# FeatherWing.net
KiCad netlist of a schematic drawn in EAGLE
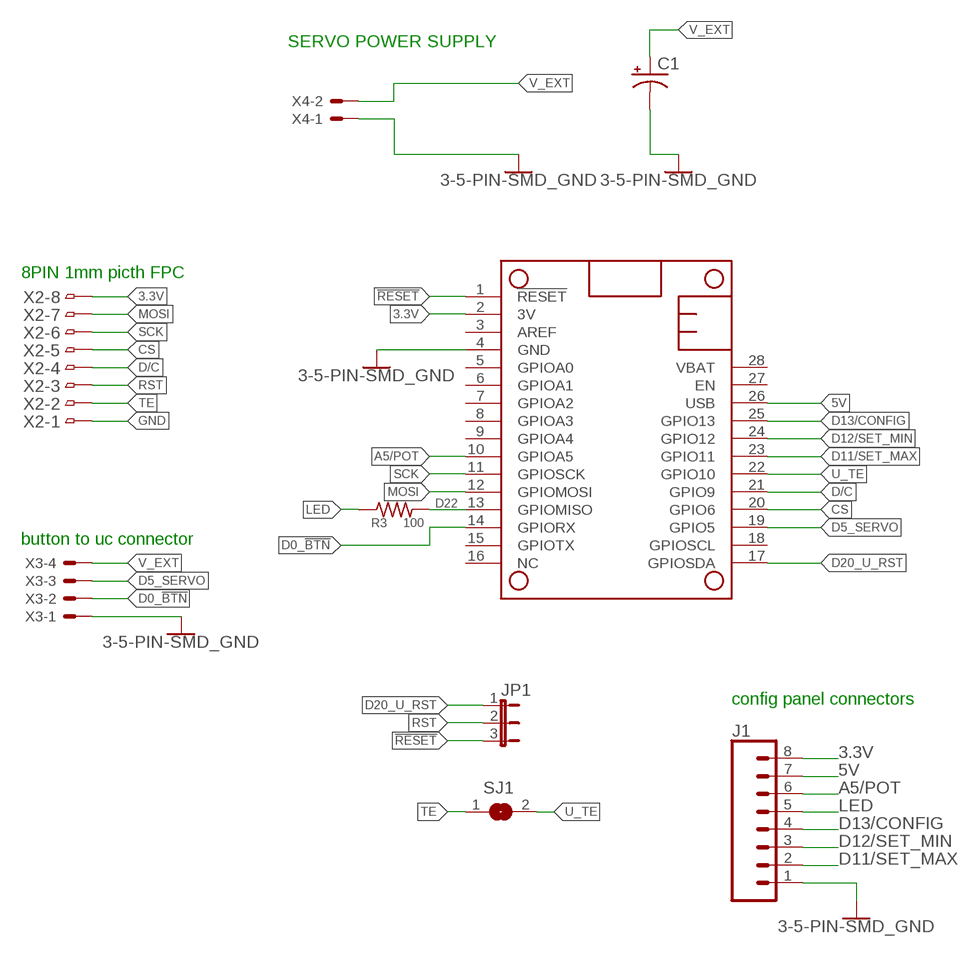
[diagram p0: schematic, sheet 1]

(export (version "E")
  (design (tool "Eeschema 10.0.6"))
  (components
    (comp (ref "C1")
      (value "ADAFRUIT_CNCT_NFP_CPOL-USC/6032-28R")
      (footprint "eagle-import:ADAFRUIT_CNCT_NFP_C_6032-28R")
      (libsource (lib "eagle-import") (part "ADAFRUIT_CNCT_NFP_CPOL-USC/6032-28R"))
    )
    (comp (ref "J1")
      (value "SPARKFUN-CONNECTORS_CONN_08LONGPADS")
      (footprint "eagle-import:SPARKFUN-CONNECTORS_1X08_LONGPADS")
      (libsource (lib "eagle-import") (part "SPARKFUN-CONNECTORS_CONN_08LONGPADS"))
    )
    (comp (ref "JP1")
      (value "LED-BADGE_SCHEMATIC_JUMPER_JP2E")
      (footprint "eagle-import:LED-BADGE_SCHEMATIC_JUMPER_JP2")
      (libsource (lib "eagle-import") (part "LED-BADGE_SCHEMATIC_JUMPER_JP2E"))
    )
    (comp (ref "MS1")
      (value "ADAFRUIT_FEATHERWING")
      (footprint "eagle-import:ADAFRUIT_FEATHERWING")
      (libsource (lib "eagle-import") (part "ADAFRUIT_FEATHERWING"))
    )
    (comp (ref "R3")
      (value "100")
      (footprint "eagle-import:AIRPOCKETCELL_ARDUINO_3V_TTL_INTERFACE_2_PI_ADAFRUIT_M0805")
      (libsource (lib "eagle-import") (part "AIRPOCKETCELL_ARDUINO_3V_TTL_INTERFACE_2_PI_ADAFRUIT_R-US_M0805"))
    )
    (comp (ref "SJ1")
      (value "AIRPOCKETCELL_JUMPER_SJW")
      (footprint "eagle-import:AIRPOCKETCELL_JUMPER_SJW")
      (libsource (lib "eagle-import") (part "AIRPOCKETCELL_JUMPER_SJW"))
    )
    (comp (ref "X2")
      (value "LEDMATRIXFPCCONNECTOR_CON-HIROSE_FH12-08S-1SH")
      (footprint "eagle-import:LEDMATRIXFPCCONNECTOR_CON-HIROSE_FH12-08S-1SH")
      (libsource (lib "eagle-import") (part "LEDMATRIXFPCCONNECTOR_CON-HIROSE_FH12-08S-1SH"))
    )
    (comp (ref "X3")
      (value "REMBRANDT-ELECTRONICS---JST-XH-CONNECTORS-V1-0_JST-XH-04-PIN-LONG-PAD")
      (footprint "eagle-import:REMBRANDT-ELECTRONICS---JST-XH-CONNECTORS-V1-0_JST-XH-04-PACKAGE-LONG-PAD")
      (libsource (lib "eagle-import") (part "REMBRANDT-ELECTRONICS---JST-XH-CONNECTORS-V1-0_JST-XH-04-PIN-LONG-PAD"))
    )
    (comp (ref "X4")
      (value "REMBRANDT-ELECTRONICS---JST-XH-CONNECTORS-V1-0_JST-XH-02-PIN-LONG-PAD")
      (footprint "eagle-import:REMBRANDT-ELECTRONICS---JST-XH-CONNECTORS-V1-0_JST-XH-02-PACKAGE-LONG-PAD")
      (libsource (lib "eagle-import") (part "REMBRANDT-ELECTRONICS---JST-XH-CONNECTORS-V1-0_JST-XH-02-PIN-LONG-PAD"))
    )
  )
  (nets
    (net (code "1") (name "/D0_~{BTN}") (class "Default")
      (node (ref "MS1") (pin "14") (pinfunction "GPIORX_14") (pintype "bidirectional"))
      (node (ref "X3") (pin "2") (pinfunction "S_2") (pintype "passive"))
    )
    (net (code "2") (name "/D22") (class "Default")
      (node (ref "MS1") (pin "13") (pinfunction "GPIOMISO_13") (pintype "bidirectional"))
      (node (ref "R3") (pin "2") (pinfunction "2_2") (pintype "passive"))
    )
    (net (code "3") (name "/VBAT") (class "Default")
      (node (ref "MS1") (pin "28") (pinfunction "VBAT_28") (pintype "power_in"))
    )
    (net (code "4") (name "/~{RESET}") (class "Default")
      (node (ref "JP1") (pin "3") (pinfunction "3_3") (pintype "passive"))
      (node (ref "MS1") (pin "1") (pinfunction "~{RESET}_1") (pintype "input"))
    )
    (net (code "5") (name "3.3V") (class "Default")
      (node (ref "J1") (pin "8") (pinfunction "8_8") (pintype "passive"))
      (node (ref "MS1") (pin "2") (pinfunction "3V_2") (pintype "power_in"))
      (node (ref "X2") (pin "8") (pinfunction "1_8") (pintype "passive"))
    )
    (net (code "6") (name "5V") (class "Default")
      (node (ref "J1") (pin "7") (pinfunction "7_7") (pintype "passive"))
      (node (ref "MS1") (pin "26") (pinfunction "USB_26") (pintype "power_in"))
    )
    (net (code "7") (name "A5{slash}POT") (class "Default")
      (node (ref "J1") (pin "6") (pinfunction "6_6") (pintype "passive"))
      (node (ref "MS1") (pin "10") (pinfunction "GPIOA5_10") (pintype "bidirectional"))
    )
    (net (code "8") (name "CS") (class "Default")
      (node (ref "MS1") (pin "20") (pinfunction "GPIO6_20") (pintype "bidirectional"))
      (node (ref "X2") (pin "5") (pinfunction "1_5") (pintype "passive"))
    )
    (net (code "9") (name "D5_SERVO") (class "Default")
      (node (ref "MS1") (pin "19") (pinfunction "GPIO5_19") (pintype "bidirectional"))
      (node (ref "X3") (pin "3") (pinfunction "S_3") (pintype "passive"))
    )
    (net (code "10") (name "D11{slash}SET_MAX") (class "Default")
      (node (ref "J1") (pin "2") (pinfunction "2_2") (pintype "passive"))
      (node (ref "MS1") (pin "23") (pinfunction "GPIO11_23") (pintype "bidirectional"))
    )
    (net (code "11") (name "D12{slash}SET_MIN") (class "Default")
      (node (ref "J1") (pin "3") (pinfunction "3_3") (pintype "passive"))
      (node (ref "MS1") (pin "24") (pinfunction "GPIO12_24") (pintype "bidirectional"))
    )
    (net (code "12") (name "D13{slash}CONFIG") (class "Default")
      (node (ref "J1") (pin "4") (pinfunction "4_4") (pintype "passive"))
      (node (ref "MS1") (pin "25") (pinfunction "GPIO13_25") (pintype "bidirectional"))
    )
    (net (code "13") (name "D20_U_RST") (class "Default")
      (node (ref "JP1") (pin "1") (pinfunction "1_1") (pintype "passive"))
      (node (ref "MS1") (pin "17") (pinfunction "GPIOSDA_17") (pintype "bidirectional"))
    )
    (net (code "14") (name "D{slash}C") (class "Default")
      (node (ref "MS1") (pin "21") (pinfunction "GPIO9_21") (pintype "bidirectional"))
      (node (ref "X2") (pin "4") (pinfunction "1_4") (pintype "passive"))
    )
    (net (code "15") (name "GND") (class "Default")
      (node (ref "C1") (pin "-") (pinfunction "-_-") (pintype "passive"))
      (node (ref "J1") (pin "1") (pinfunction "1_1") (pintype "passive"))
      (node (ref "MS1") (pin "4") (pinfunction "GND_4") (pintype "power_in"))
      (node (ref "X2") (pin "1") (pinfunction "1_1") (pintype "passive"))
      (node (ref "X3") (pin "1") (pinfunction "S_1") (pintype "passive"))
      (node (ref "X4") (pin "1") (pinfunction "S_1") (pintype "passive"))
    )
    (net (code "16") (name "LED") (class "Default")
      (node (ref "J1") (pin "5") (pinfunction "5_5") (pintype "passive"))
      (node (ref "R3") (pin "1") (pinfunction "1_1") (pintype "passive"))
    )
    (net (code "17") (name "MOSI") (class "Default")
      (node (ref "MS1") (pin "12") (pinfunction "GPIOMOSI_12") (pintype "bidirectional"))
      (node (ref "X2") (pin "7") (pinfunction "1_7") (pintype "passive"))
    )
    (net (code "18") (name "RST") (class "Default")
      (node (ref "JP1") (pin "2") (pinfunction "2_2") (pintype "passive"))
      (node (ref "X2") (pin "3") (pinfunction "1_3") (pintype "passive"))
    )
    (net (code "19") (name "SCK") (class "Default")
      (node (ref "MS1") (pin "11") (pinfunction "GPIOSCK_11") (pintype "bidirectional"))
      (node (ref "X2") (pin "6") (pinfunction "1_6") (pintype "passive"))
    )
    (net (code "20") (name "TE") (class "Default")
      (node (ref "SJ1") (pin "1") (pinfunction "1_1") (pintype "passive"))
      (node (ref "X2") (pin "2") (pinfunction "1_2") (pintype "passive"))
    )
    (net (code "21") (name "U_TE") (class "Default")
      (node (ref "MS1") (pin "22") (pinfunction "GPIO10_22") (pintype "bidirectional"))
      (node (ref "SJ1") (pin "2") (pinfunction "2_2") (pintype "passive"))
    )
    (net (code "22") (name "V_EXT") (class "Default")
      (node (ref "C1") (pin "+") (pinfunction "+_+") (pintype "passive"))
      (node (ref "X3") (pin "4") (pinfunction "S_4") (pintype "passive"))
      (node (ref "X4") (pin "2") (pinfunction "S_2") (pintype "passive"))
    )
    (net (code "23") (name "unconnected-(MS1-AREF-Pad3)") (class "Default")
      (node (ref "MS1") (pin "3") (pinfunction "AREF_3") (pintype "passive"))
    )
    (net (code "24") (name "unconnected-(MS1-EN-Pad27)") (class "Default")
      (node (ref "MS1") (pin "27") (pinfunction "EN_27") (pintype "passive"))
    )
    (net (code "25") (name "unconnected-(MS1-GPIOA0-Pad5)") (class "Default")
      (node (ref "MS1") (pin "5") (pinfunction "GPIOA0_5") (pintype "bidirectional"))
    )
    (net (code "26") (name "unconnected-(MS1-GPIOA1-Pad6)") (class "Default")
      (node (ref "MS1") (pin "6") (pinfunction "GPIOA1_6") (pintype "bidirectional"))
    )
    (net (code "27") (name "unconnected-(MS1-GPIOA2-Pad7)") (class "Default")
      (node (ref "MS1") (pin "7") (pinfunction "GPIOA2_7") (pintype "bidirectional"))
    )
    (net (code "28") (name "unconnected-(MS1-GPIOA3-Pad8)") (class "Default")
      (node (ref "MS1") (pin "8") (pinfunction "GPIOA3_8") (pintype "bidirectional"))
    )
    (net (code "29") (name "unconnected-(MS1-GPIOA4-Pad9)") (class "Default")
      (node (ref "MS1") (pin "9") (pinfunction "GPIOA4_9") (pintype "bidirectional"))
    )
    (net (code "30") (name "unconnected-(MS1-GPIOSCL-Pad18)") (class "Default")
      (node (ref "MS1") (pin "18") (pinfunction "GPIOSCL_18") (pintype "bidirectional"))
    )
    (net (code "31") (name "unconnected-(MS1-GPIOTX-Pad15)") (class "Default")
      (node (ref "MS1") (pin "15") (pinfunction "GPIOTX_15") (pintype "bidirectional"))
    )
    (net (code "32") (name "unconnected-(MS1-NC-Pad16)") (class "Default")
      (node (ref "MS1") (pin "16") (pinfunction "NC_16") (pintype "passive"))
    )
  )
)
